# Blinky.net
KiCad netlist of a schematic drawn in EAGLE
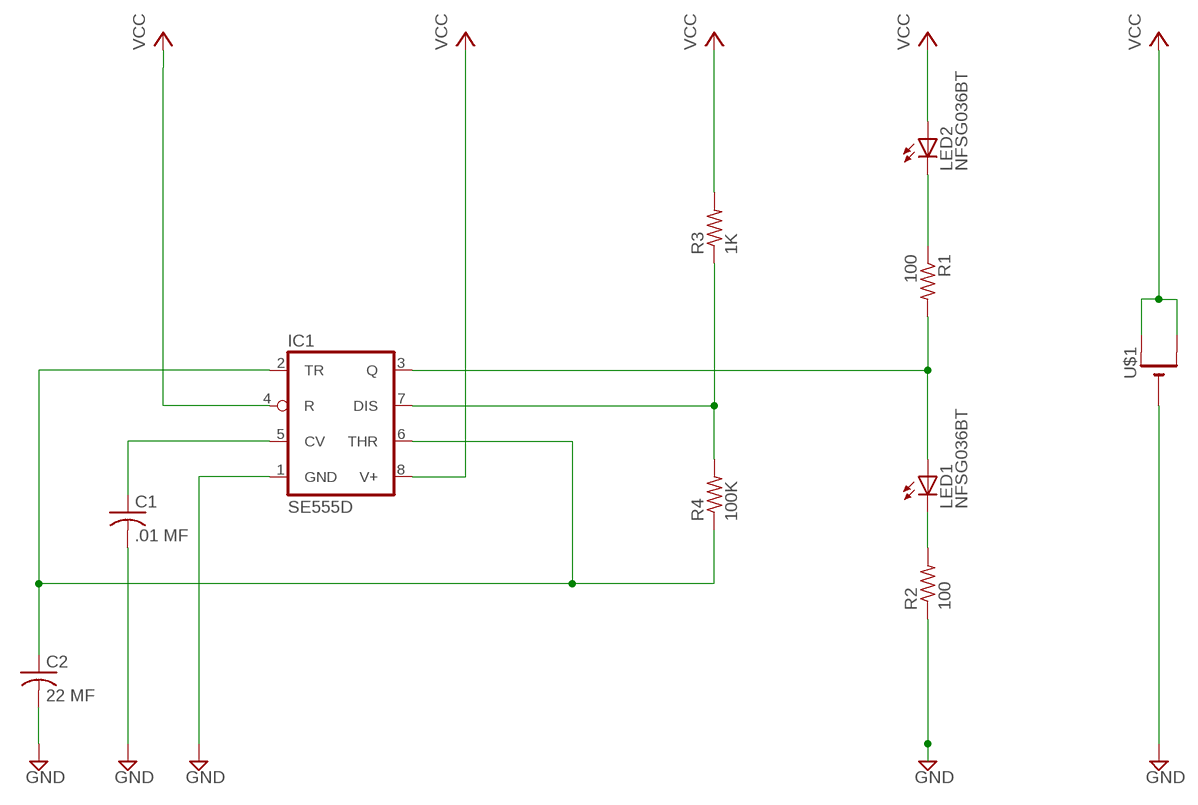
[diagram p0: schematic, sheet 1]

(export (version "E")
  (design (tool "Eeschema 10.0.6"))
  (components
    (comp (ref "C1")
      (value ".01 MF")
      (footprint "eagle-import:C0805")
      (fields (field (name "MPN") "885012007009"))
      (libsource (lib "eagle-import") (part "C-USC0805"))
    )
    (comp (ref "C2")
      (value "22 MF")
      (footprint "eagle-import:C0805")
      (fields (field (name "MPN") "GRT21BR60J226ME13L"))
      (libsource (lib "eagle-import") (part "C-USC0805"))
    )
    (comp (ref "IC1")
      (value "SE555D")
      (footprint "eagle-import:SO08")
      (fields (field (name "MF") "FARNELL") (field (name "MPN") "TLC555CDR"))
      (libsource (lib "eagle-import") (part "555DSE"))
    )
    (comp (ref "LED1")
      (value "NFSG036BT")
      (footprint "eagle-import:NFSG036BT")
      (fields (field (name "MPN") "KPTD-2012ZGCK"))
      (libsource (lib "eagle-import") (part "NFSG036BT"))
    )
    (comp (ref "LED2")
      (value "NFSG036BT")
      (footprint "eagle-import:NFSG036BT")
      (fields (field (name "MPN") "KPTD-2012ZGCK"))
      (libsource (lib "eagle-import") (part "NFSG036BT"))
    )
    (comp (ref "R1")
      (value "100")
      (footprint "eagle-import:M0805")
      (fields (field (name "MPN") "MCTF0805BTC1000"))
      (libsource (lib "eagle-import") (part "R-US_M0805"))
    )
    (comp (ref "R2")
      (value "100")
      (footprint "eagle-import:M0805")
      (fields (field (name "MPN") "MCTF0805BTC1000"))
      (libsource (lib "eagle-import") (part "R-US_M0805"))
    )
    (comp (ref "R3")
      (value "1K")
      (footprint "eagle-import:M0805")
      (fields (field (name "MF") "VISHAY/DALE") (field (name "MPN") "CRCW08051K00FKTA"))
      (libsource (lib "eagle-import") (part "R-US_M0805"))
    )
    (comp (ref "R4")
      (value "100K")
      (footprint "eagle-import:M0805")
      (fields (field (name "MPN") "CRCW0805100KFKTA"))
      (libsource (lib "eagle-import") (part "R-US_M0805"))
    )
    (comp (ref "U$1")
      (value "CR1220THM")
      (footprint "eagle-import:CR1220-THM")
      (fields (field (name "MF") "KEYSTONE ELECTR") (field (name "MPN") "500"))
      (libsource (lib "eagle-import") (part "CR1220THM"))
    )
  )
  (nets
    (net (code "1") (name "GND") (class "Default")
      (node (ref "C1") (pin "2") (pinfunction "2_2") (pintype "passive"))
      (node (ref "C2") (pin "2") (pinfunction "2_2") (pintype "passive"))
      (node (ref "IC1") (pin "1") (pinfunction "GND_1") (pintype "power_in"))
      (node (ref "R2") (pin "1") (pinfunction "1_1") (pintype "passive"))
      (node (ref "U$1") (pin "-") (pinfunction "-_-") (pintype "passive"))
    )
    (net (code "2") (name "Net-(IC1-CV)") (class "Default")
      (node (ref "C1") (pin "1") (pinfunction "1_1") (pintype "passive"))
      (node (ref "IC1") (pin "5") (pinfunction "CV_5") (pintype "input"))
    )
    (net (code "3") (name "Net-(IC1-DIS)") (class "Default")
      (node (ref "IC1") (pin "7") (pinfunction "DIS_7") (pintype "input"))
      (node (ref "R3") (pin "1") (pinfunction "1_1") (pintype "passive"))
      (node (ref "R4") (pin "2") (pinfunction "2_2") (pintype "passive"))
    )
    (net (code "4") (name "Net-(IC1-Q)") (class "Default")
      (node (ref "IC1") (pin "3") (pinfunction "Q_3") (pintype "output"))
      (node (ref "LED1") (pin "A") (pinfunction "A_A") (pintype "passive"))
      (node (ref "R1") (pin "2") (pinfunction "2_2") (pintype "passive"))
    )
    (net (code "5") (name "Net-(IC1-THR)") (class "Default")
      (node (ref "C2") (pin "1") (pinfunction "1_1") (pintype "passive"))
      (node (ref "IC1") (pin "2") (pinfunction "TR_2") (pintype "input"))
      (node (ref "IC1") (pin "6") (pinfunction "THR_6") (pintype "input"))
      (node (ref "R4") (pin "1") (pinfunction "1_1") (pintype "passive"))
    )
    (net (code "6") (name "Net-(LED1-PadC)") (class "Default")
      (node (ref "LED1") (pin "C") (pinfunction "C_C") (pintype "passive"))
      (node (ref "R2") (pin "2") (pinfunction "2_2") (pintype "passive"))
    )
    (net (code "7") (name "Net-(LED2-PadC)") (class "Default")
      (node (ref "LED2") (pin "C") (pinfunction "C_C") (pintype "passive"))
      (node (ref "R1") (pin "1") (pinfunction "1_1") (pintype "passive"))
    )
    (net (code "8") (name "VCC") (class "Default")
      (node (ref "IC1") (pin "4") (pinfunction "R_4") (pintype "input"))
      (node (ref "IC1") (pin "8") (pinfunction "V+_8") (pintype "power_in"))
      (node (ref "LED2") (pin "A") (pinfunction "A_A") (pintype "passive"))
      (node (ref "R3") (pin "2") (pinfunction "2_2") (pintype "passive"))
      (node (ref "U$1") (pin "+1") (pinfunction "+_+1") (pintype "passive"))
      (node (ref "U$1") (pin "+2") (pinfunction "+1_+2") (pintype "passive"))
    )
  )
)
